# LoRa.net
KiCad netlist of a schematic drawn in Altium Designer
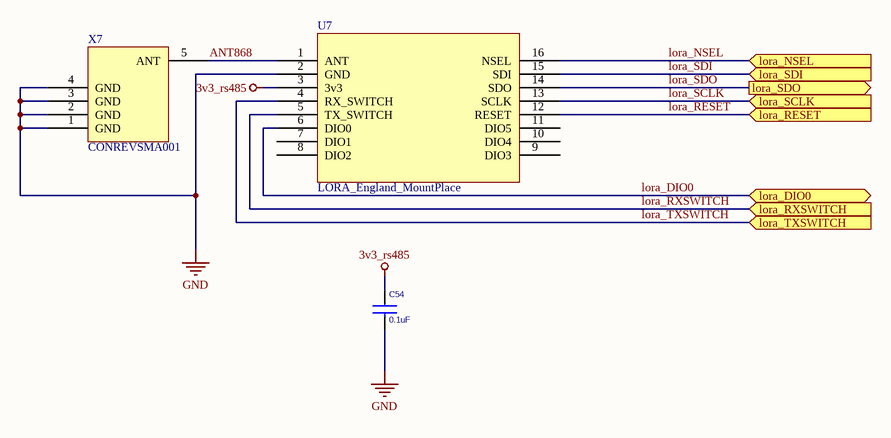
[diagram p0: LoRa.SchDoc]

(export (version "E")
  (design (tool "Eeschema 10.0.6"))
  (components
    (comp (ref "C54")
      (value "0.1uF")
      (footprint "CAPC2012X09M")
      (description "CAP CER 0.1UF 25V 10% X7R 0805")
      (libsource (lib "Capacitors") (part "CAP_SMD_0.1UF_10%"))
    )
    (comp (ref "U7")
      (value "LORA_England_MountPlace")
      (footprint "DIP16")
      (libsource (lib "TruthEar") (part "LORA_MODULE_E"))
    )
    (comp (ref "X7")
      (value "CONREVSMA001")
      (footprint "SMA6252A2-3GT50G-50")
      (libsource (lib "Connectors") (part "SMA_CONN"))
    )
  )
  (nets
    (net (code "1") (name "/ANT868") (class "Default")
      (node (ref "U7") (pin "1") (pinfunction "ANT_1") (pintype "passive"))
      (node (ref "X7") (pin "5") (pinfunction "ANT_5") (pintype "passive"))
    )
    (net (code "2") (name "/lora_DIO0") (class "Default")
      (node (ref "U7") (pin "6") (pinfunction "DIO0_6") (pintype "passive"))
    )
    (net (code "3") (name "/lora_NSEL") (class "Default")
      (node (ref "U7") (pin "16") (pinfunction "NSEL_16") (pintype "passive"))
    )
    (net (code "4") (name "/lora_RESET") (class "Default")
      (node (ref "U7") (pin "12") (pinfunction "RESET_12") (pintype "passive"))
    )
    (net (code "5") (name "/lora_RXSWITCH") (class "Default")
      (node (ref "U7") (pin "5") (pinfunction "TX_SWITCH_5") (pintype "passive"))
    )
    (net (code "6") (name "/lora_SCLK") (class "Default")
      (node (ref "U7") (pin "13") (pinfunction "SCLK_13") (pintype "passive"))
    )
    (net (code "7") (name "/lora_SDI") (class "Default")
      (node (ref "U7") (pin "15") (pinfunction "SDI_15") (pintype "passive"))
    )
    (net (code "8") (name "/lora_SDO") (class "Default")
      (node (ref "U7") (pin "14") (pinfunction "SDO_14") (pintype "passive"))
    )
    (net (code "9") (name "/lora_TXSWITCH") (class "Default")
      (node (ref "U7") (pin "4") (pinfunction "RX_SWITCH_4") (pintype "passive"))
    )
    (net (code "10") (name "3v3_rs485") (class "Default")
      (node (ref "C54") (pin "1") (pinfunction "1_1") (pintype "passive"))
      (node (ref "U7") (pin "3") (pinfunction "3v3_3") (pintype "passive"))
    )
    (net (code "11") (name "GND") (class "Default")
      (node (ref "C54") (pin "2") (pinfunction "2_2") (pintype "passive"))
      (node (ref "U7") (pin "2") (pinfunction "GND_2") (pintype "passive"))
      (node (ref "X7") (pin "1") (pinfunction "GND_1") (pintype "passive"))
      (node (ref "X7") (pin "2") (pinfunction "GND_2") (pintype "passive"))
      (node (ref "X7") (pin "3") (pinfunction "GND_3") (pintype "passive"))
      (node (ref "X7") (pin "4") (pinfunction "GND_4") (pintype "passive"))
    )
    (net (code "12") (name "unconnected-(U7-DIO1-Pad7)") (class "Default")
      (node (ref "U7") (pin "7") (pinfunction "DIO1_7") (pintype "passive"))
    )
    (net (code "13") (name "unconnected-(U7-DIO2-Pad8)") (class "Default")
      (node (ref "U7") (pin "8") (pinfunction "DIO2_8") (pintype "passive"))
    )
    (net (code "14") (name "unconnected-(U7-DIO3-Pad9)") (class "Default")
      (node (ref "U7") (pin "9") (pinfunction "DIO3_9") (pintype "passive"))
    )
    (net (code "15") (name "unconnected-(U7-DIO4-Pad10)") (class "Default")
      (node (ref "U7") (pin "10") (pinfunction "DIO4_10") (pintype "passive"))
    )
    (net (code "16") (name "unconnected-(U7-DIO5-Pad11)") (class "Default")
      (node (ref "U7") (pin "11") (pinfunction "DIO5_11") (pintype "passive"))
    )
  )
)
